# zLineIn_fp_00.net
KiCad netlist of a schematic drawn in EAGLE
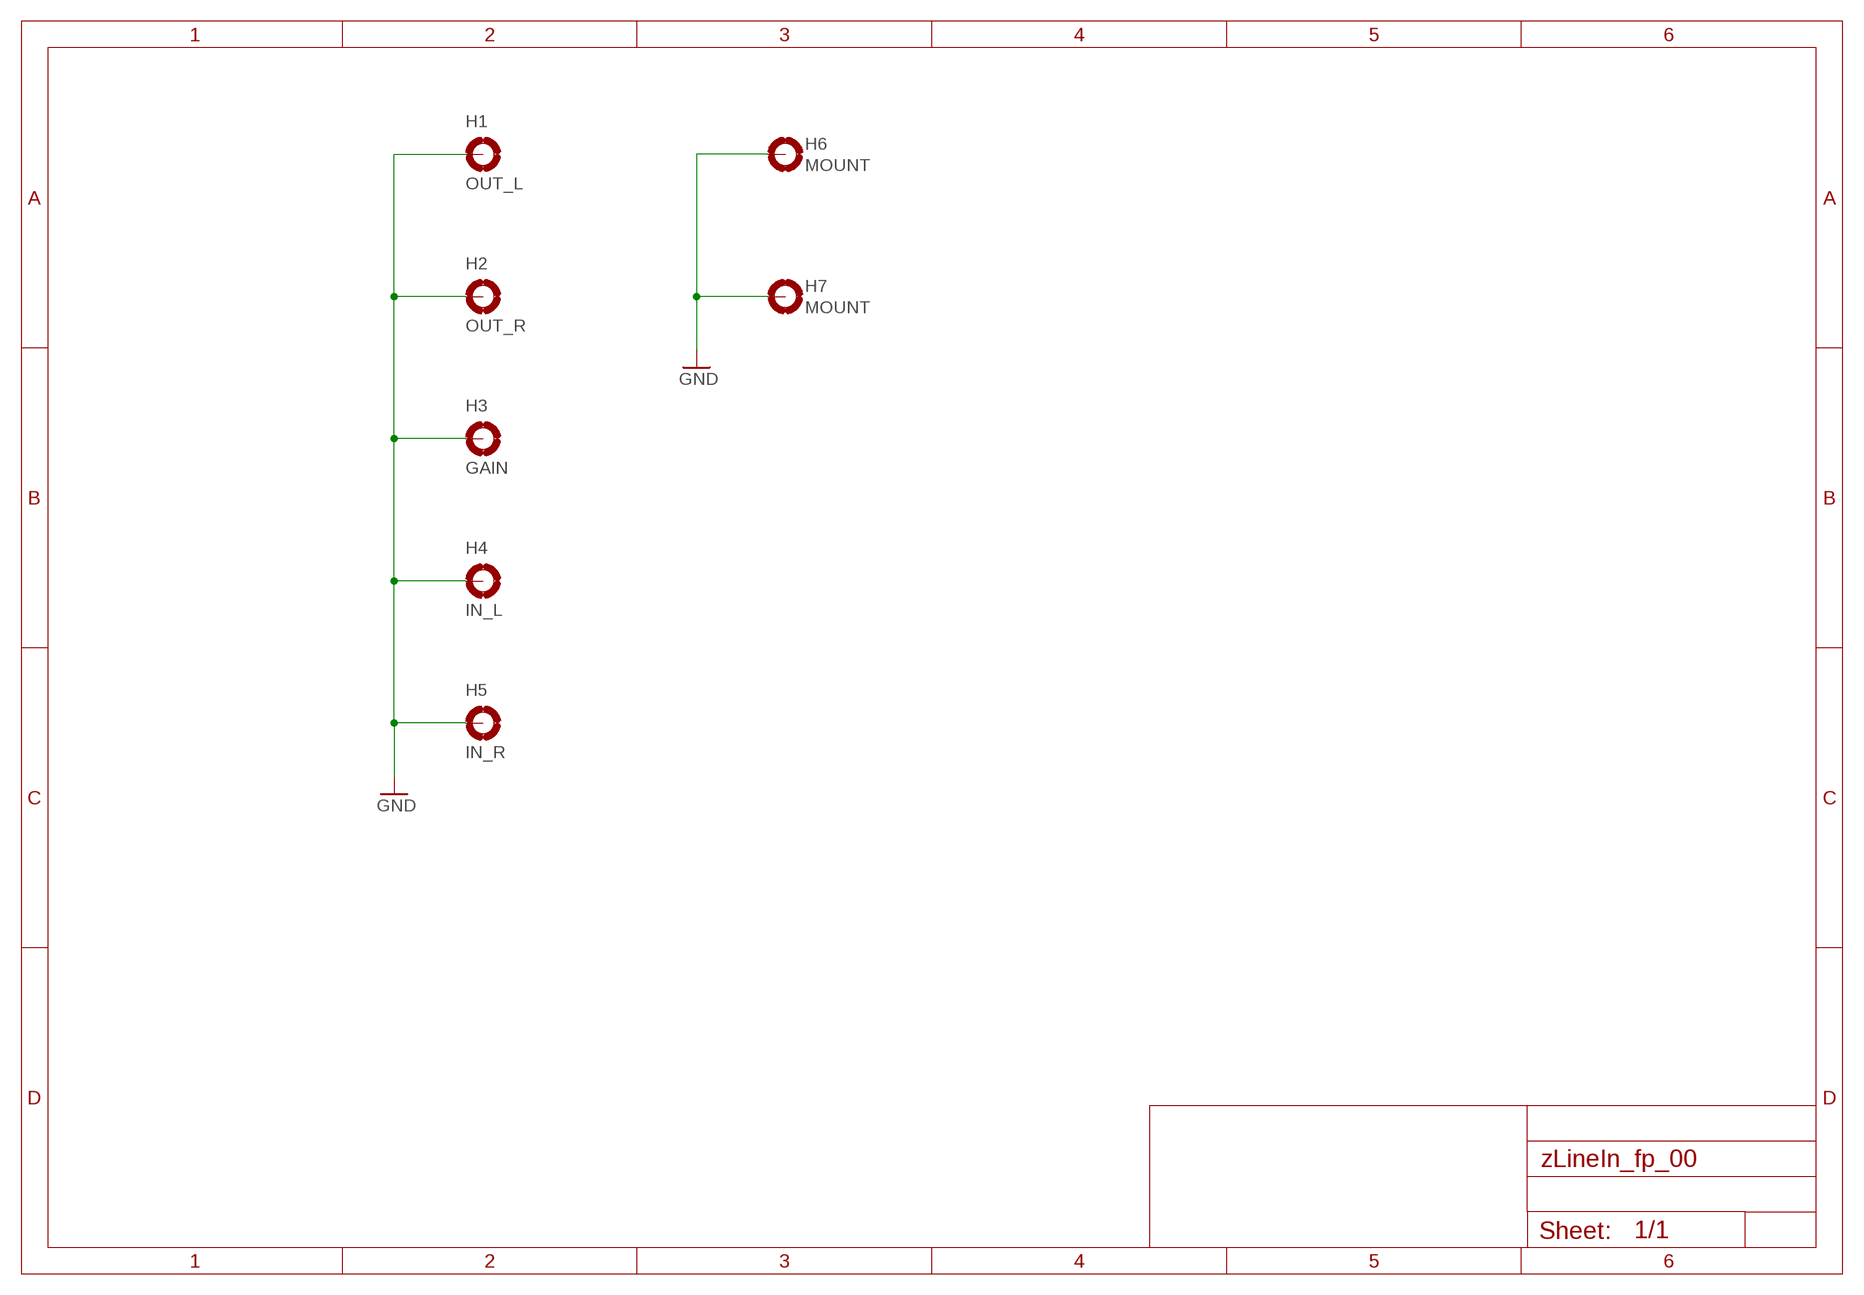
[diagram p0: schematic, sheet 1]

(export (version "E")
  (design (tool "Eeschema 10.0.6"))
  (components
    (comp (ref "H1")
      (value "OUT_L")
      (footprint "eagle-import:6,223-PAD")
      (libsource (lib "eagle-import") (part "MOUNT-PAD-ROUND6.223"))
    )
    (comp (ref "H2")
      (value "OUT_R")
      (footprint "eagle-import:6,223-PAD")
      (libsource (lib "eagle-import") (part "MOUNT-PAD-ROUND6.223"))
    )
    (comp (ref "H3")
      (value "GAIN")
      (footprint "eagle-import:7.112-PAD")
      (libsource (lib "eagle-import") (part "MOUNT-PAD-ROUND7.112"))
    )
    (comp (ref "H4")
      (value "IN_L")
      (footprint "eagle-import:11.43-PAD")
      (libsource (lib "eagle-import") (part "MOUNT-PAD-ROUND11,43"))
    )
    (comp (ref "H5")
      (value "IN_R")
      (footprint "eagle-import:11.43-PAD")
      (libsource (lib "eagle-import") (part "MOUNT-PAD-ROUND11,43"))
    )
    (comp (ref "H6")
      (value "MOUNT")
      (footprint "eagle-import:3,2-PAD_L")
      (libsource (lib "eagle-import") (part "MOUNT-PAD-LONG3.2"))
    )
    (comp (ref "H7")
      (value "MOUNT")
      (footprint "eagle-import:3,2-PAD_L")
      (libsource (lib "eagle-import") (part "MOUNT-PAD-LONG3.2"))
    )
  )
  (nets
    (net (code "1") (name "GND") (class "Default")
      (node (ref "H1") (pin "B6,223") (pinfunction "MOUNT_B6,223") (pintype "passive"))
      (node (ref "H2") (pin "B6,223") (pinfunction "MOUNT_B6,223") (pintype "passive"))
      (node (ref "H3") (pin "B4,5") (pinfunction "MOUNT_B4,5") (pintype "passive"))
      (node (ref "H4") (pin "B5,5") (pinfunction "MOUNT_B5,5") (pintype "passive"))
      (node (ref "H5") (pin "B5,5") (pinfunction "MOUNT_B5,5") (pintype "passive"))
      (node (ref "H6") (pin "B3,2") (pinfunction "MOUNT_B3,2") (pintype "passive"))
      (node (ref "H7") (pin "B3,2") (pinfunction "MOUNT_B3,2") (pintype "passive"))
    )
  )
)
